# Adapter_UARTSPI_RS485.net
KiCad netlist of a schematic drawn in EAGLE
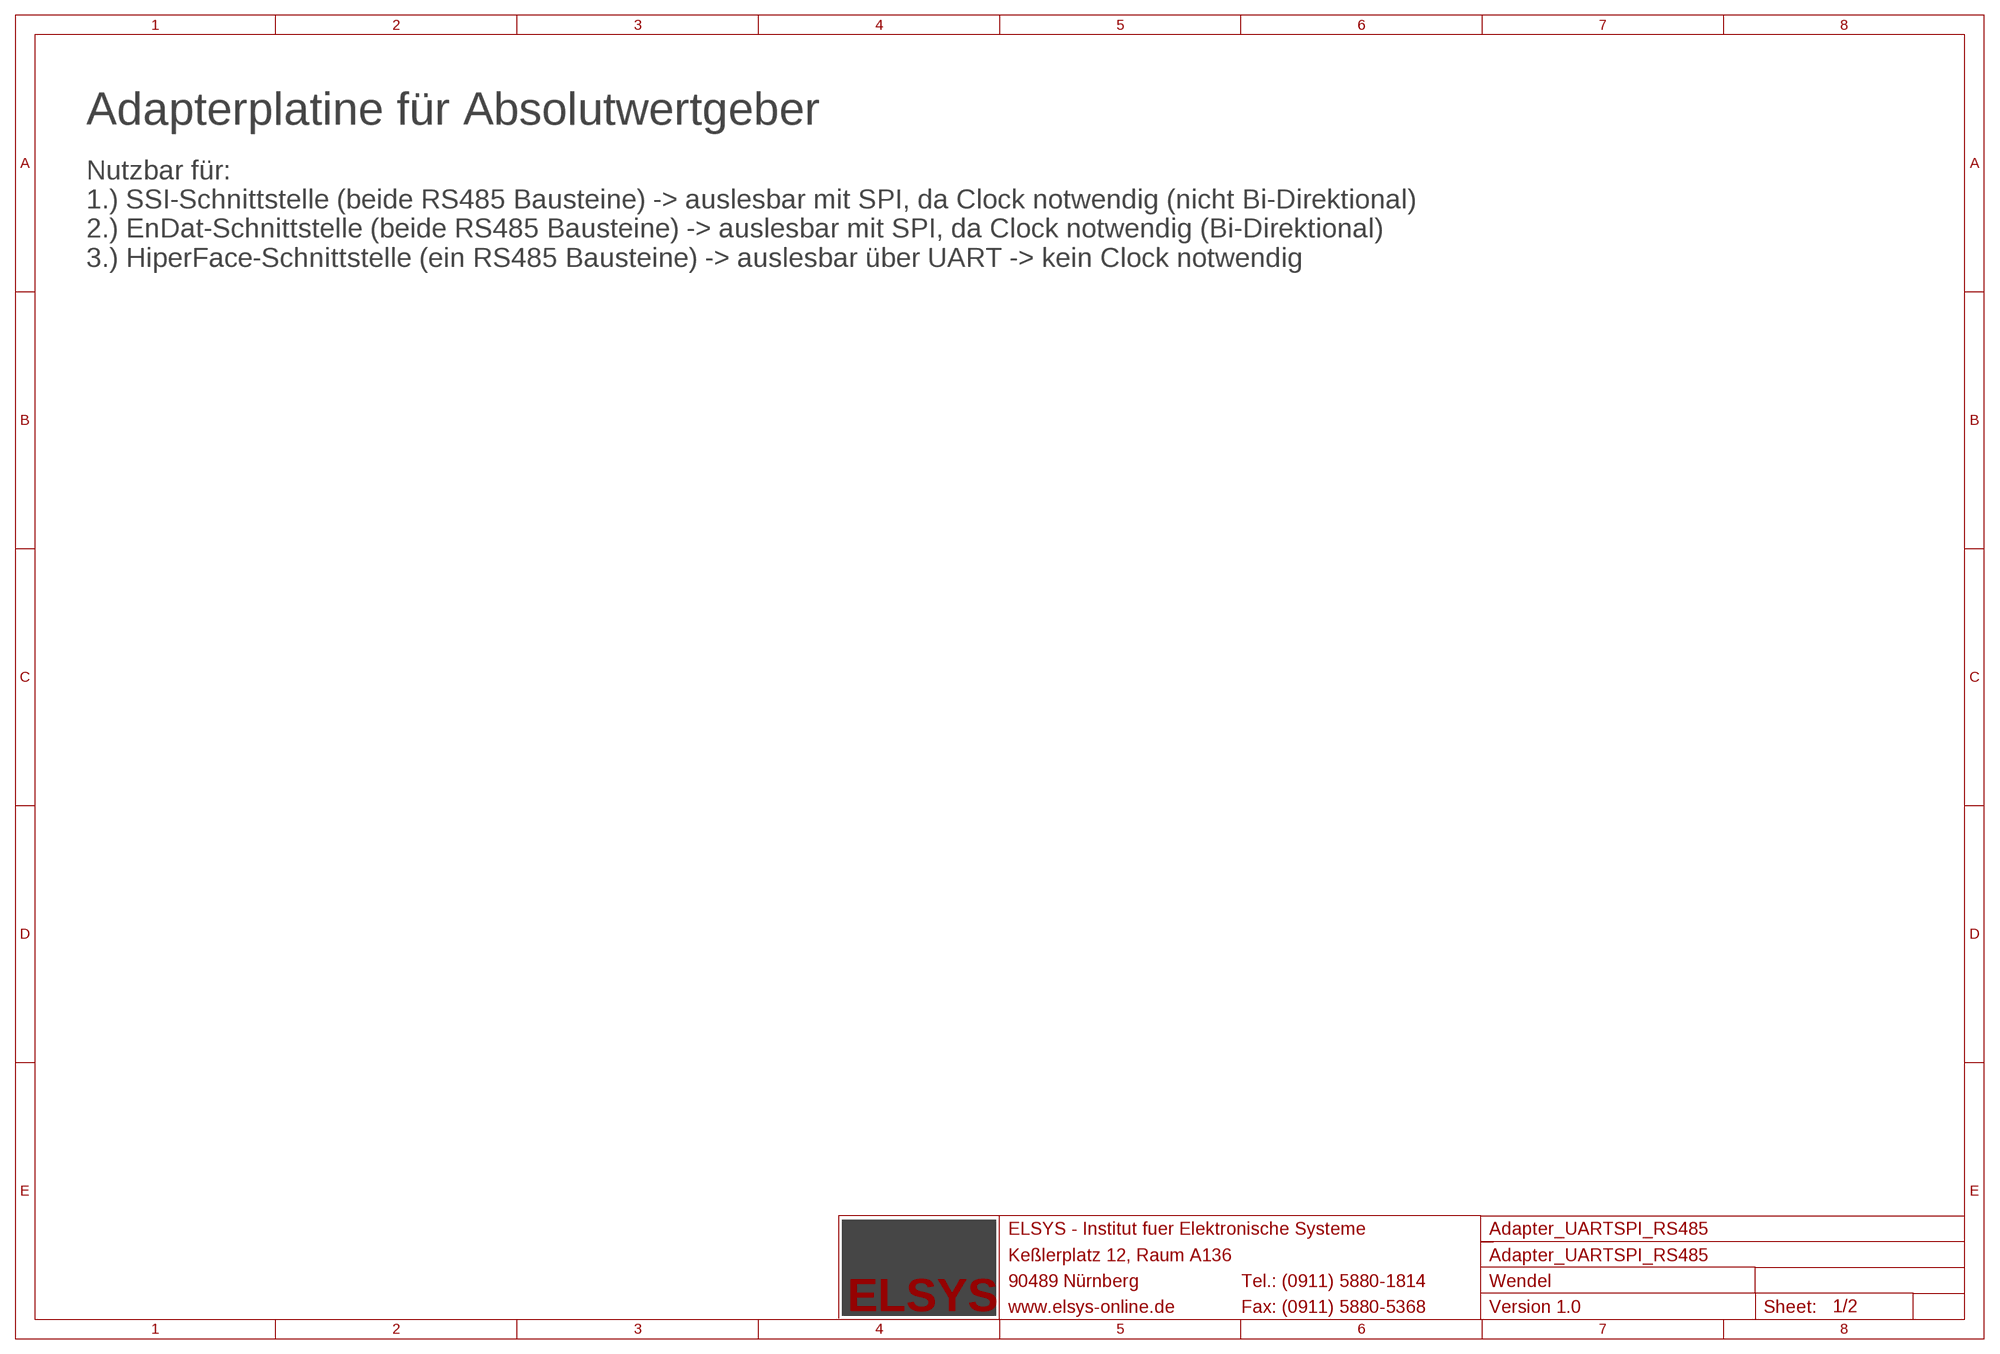
[diagram p0: schematic, sheet 1]
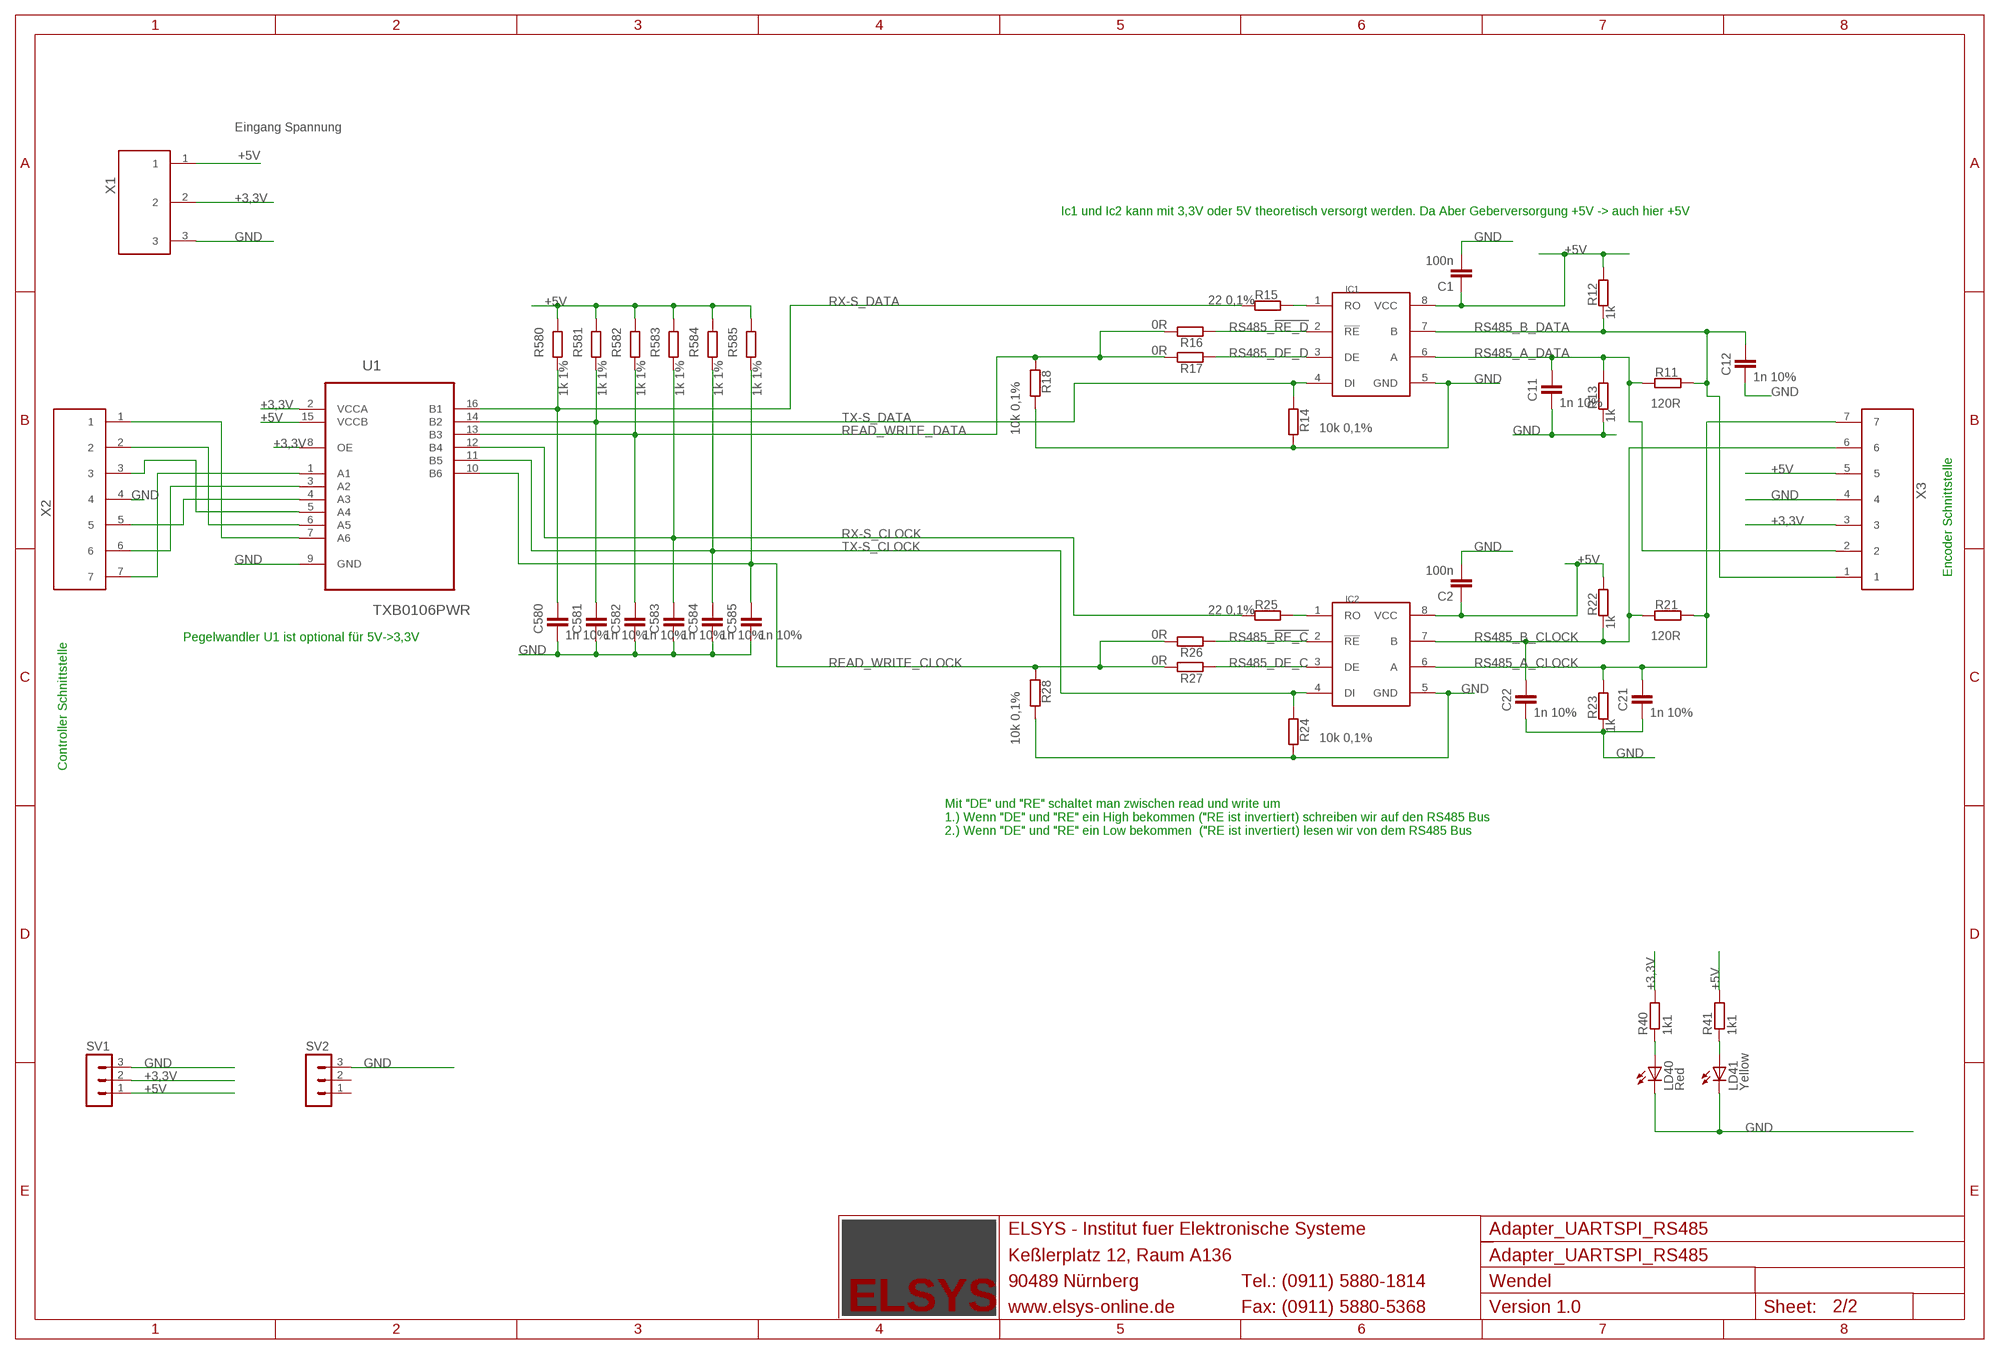
[diagram p1: schematic, sheet 2]

(export (version "E")
  (design (tool "Eeschema 10.0.6"))
  (components
    (comp (ref "C1")
      (value "100n")
      (footprint "eagle-import:SMD-0603")
      (libsource (lib "eagle-import") (part "C-EU0603"))
    )
    (comp (ref "C2")
      (value "100n")
      (footprint "eagle-import:SMD-0603")
      (libsource (lib "eagle-import") (part "C-EU0603"))
    )
    (comp (ref "C11")
      (value "1n 10%")
      (footprint "eagle-import:SMD-0603")
      (libsource (lib "eagle-import") (part "C-EU0603"))
    )
    (comp (ref "C12")
      (value "1n 10%")
      (footprint "eagle-import:SMD-0603")
      (libsource (lib "eagle-import") (part "C-EU0603"))
    )
    (comp (ref "C21")
      (value "1n 10%")
      (footprint "eagle-import:SMD-0603")
      (libsource (lib "eagle-import") (part "C-EU0603"))
    )
    (comp (ref "C22")
      (value "1n 10%")
      (footprint "eagle-import:SMD-0603")
      (libsource (lib "eagle-import") (part "C-EU0603"))
    )
    (comp (ref "C580")
      (value "1n 10%")
      (footprint "eagle-import:SMD-0603")
      (libsource (lib "eagle-import") (part "C-EU0603"))
    )
    (comp (ref "C581")
      (value "1n 10%")
      (footprint "eagle-import:SMD-0603")
      (libsource (lib "eagle-import") (part "C-EU0603"))
    )
    (comp (ref "C582")
      (value "1n 10%")
      (footprint "eagle-import:SMD-0603")
      (libsource (lib "eagle-import") (part "C-EU0603"))
    )
    (comp (ref "C583")
      (value "1n 10%")
      (footprint "eagle-import:SMD-0603")
      (libsource (lib "eagle-import") (part "C-EU0603"))
    )
    (comp (ref "C584")
      (value "1n 10%")
      (footprint "eagle-import:SMD-0603")
      (libsource (lib "eagle-import") (part "C-EU0603"))
    )
    (comp (ref "C585")
      (value "1n 10%")
      (footprint "eagle-import:SMD-0603")
      (libsource (lib "eagle-import") (part "C-EU0603"))
    )
    (comp (ref "IC1")
      (value "RS485-MAXIM")
      (footprint "eagle-import:SOIC8")
      (libsource (lib "eagle-import") (part "RS485-MAXIM"))
    )
    (comp (ref "IC2")
      (value "RS485-MAXIM")
      (footprint "eagle-import:SOIC8")
      (libsource (lib "eagle-import") (part "RS485-MAXIM"))
    )
    (comp (ref "LD40")
      (value "Red")
      (footprint "eagle-import:CHIP-LED0805")
      (libsource (lib "eagle-import") (part "LEDCHIP-LED0805"))
    )
    (comp (ref "LD41")
      (value "Yellow")
      (footprint "eagle-import:CHIP-LED0805")
      (libsource (lib "eagle-import") (part "LEDCHIP-LED0805"))
    )
    (comp (ref "R11")
      (value "120R")
      (footprint "eagle-import:R0603")
      (libsource (lib "eagle-import") (part "R-EU_R0603"))
    )
    (comp (ref "R12")
      (value "1k")
      (footprint "eagle-import:R0603")
      (libsource (lib "eagle-import") (part "R-EU_R0603"))
    )
    (comp (ref "R13")
      (value "1k")
      (footprint "eagle-import:R0603")
      (libsource (lib "eagle-import") (part "R-EU_R0603"))
    )
    (comp (ref "R14")
      (value "10k 0,1%")
      (footprint "eagle-import:R0603")
      (libsource (lib "eagle-import") (part "R-EU_R0603"))
    )
    (comp (ref "R15")
      (value "22 0,1%")
      (footprint "eagle-import:R0603")
      (libsource (lib "eagle-import") (part "R-EU_R0603"))
    )
    (comp (ref "R16")
      (value "0R")
      (footprint "eagle-import:R0603")
      (libsource (lib "eagle-import") (part "R-EU_R0603"))
    )
    (comp (ref "R17")
      (value "0R")
      (footprint "eagle-import:R0603")
      (libsource (lib "eagle-import") (part "R-EU_R0603"))
    )
    (comp (ref "R18")
      (value "10k 0,1%")
      (footprint "eagle-import:R0603")
      (libsource (lib "eagle-import") (part "R-EU_R0603"))
    )
    (comp (ref "R21")
      (value "120R")
      (footprint "eagle-import:R0603")
      (libsource (lib "eagle-import") (part "R-EU_R0603"))
    )
    (comp (ref "R22")
      (value "1k")
      (footprint "eagle-import:R0603")
      (libsource (lib "eagle-import") (part "R-EU_R0603"))
    )
    (comp (ref "R23")
      (value "1k")
      (footprint "eagle-import:R0603")
      (libsource (lib "eagle-import") (part "R-EU_R0603"))
    )
    (comp (ref "R24")
      (value "10k 0,1%")
      (footprint "eagle-import:R0603")
      (libsource (lib "eagle-import") (part "R-EU_R0603"))
    )
    (comp (ref "R25")
      (value "22 0,1%")
      (footprint "eagle-import:R0603")
      (libsource (lib "eagle-import") (part "R-EU_R0603"))
    )
    (comp (ref "R26")
      (value "0R")
      (footprint "eagle-import:R0603")
      (libsource (lib "eagle-import") (part "R-EU_R0603"))
    )
    (comp (ref "R27")
      (value "0R")
      (footprint "eagle-import:R0603")
      (libsource (lib "eagle-import") (part "R-EU_R0603"))
    )
    (comp (ref "R28")
      (value "10k 0,1%")
      (footprint "eagle-import:R0603")
      (libsource (lib "eagle-import") (part "R-EU_R0603"))
    )
    (comp (ref "R40")
      (value "1k1")
      (footprint "eagle-import:R0805")
      (libsource (lib "eagle-import") (part "R-EU_R0805"))
    )
    (comp (ref "R41")
      (value "1k1")
      (footprint "eagle-import:R0805")
      (libsource (lib "eagle-import") (part "R-EU_R0805"))
    )
    (comp (ref "R580")
      (value "1k 1%")
      (footprint "eagle-import:R0603")
      (libsource (lib "eagle-import") (part "R-EU_R0603"))
    )
    (comp (ref "R581")
      (value "1k 1%")
      (footprint "eagle-import:R0603")
      (libsource (lib "eagle-import") (part "R-EU_R0603"))
    )
    (comp (ref "R582")
      (value "1k 1%")
      (footprint "eagle-import:R0603")
      (libsource (lib "eagle-import") (part "R-EU_R0603"))
    )
    (comp (ref "R583")
      (value "1k 1%")
      (footprint "eagle-import:R0603")
      (libsource (lib "eagle-import") (part "R-EU_R0603"))
    )
    (comp (ref "R584")
      (value "1k 1%")
      (footprint "eagle-import:R0603")
      (libsource (lib "eagle-import") (part "R-EU_R0603"))
    )
    (comp (ref "R585")
      (value "1k 1%")
      (footprint "eagle-import:R0603")
      (libsource (lib "eagle-import") (part "R-EU_R0603"))
    )
    (comp (ref "SV1")
      (value "MA03-1")
      (footprint "eagle-import:MA03-1")
      (libsource (lib "eagle-import") (part "MA03-1"))
    )
    (comp (ref "SV2")
      (value "MA03-1")
      (footprint "eagle-import:MA03-1")
      (libsource (lib "eagle-import") (part "MA03-1"))
    )
    (comp (ref "U1")
      (value "TXB0106PWR")
      (footprint "eagle-import:SOP65P640X120-16N")
      (libsource (lib "eagle-import") (part "TXB0106PWR"))
    )
    (comp (ref "X1")
      (value "KLEMME_3POLIG_2,54")
      (footprint "eagle-import:KLEMME_3POLIG_2,54")
      (libsource (lib "eagle-import") (part "KLEMME_3POLIG_2,54"))
    )
    (comp (ref "X2")
      (value "KLEMME_7POLIG_2,54")
      (footprint "eagle-import:KLEMME_7POLIG_2,54")
      (libsource (lib "eagle-import") (part "KLEMME_7POLIG_2,54"))
    )
    (comp (ref "X3")
      (value "KLEMME_7POLIG_2,54")
      (footprint "eagle-import:KLEMME_7POLIG_2,54")
      (libsource (lib "eagle-import") (part "KLEMME_7POLIG_2,54"))
    )
  )
  (nets
    (net (code "1") (name "+3,3V") (class "Default")
      (node (ref "R40") (pin "2") (pinfunction "2_2") (pintype "passive"))
      (node (ref "SV1") (pin "2") (pinfunction "2_2") (pintype "passive"))
      (node (ref "U1") (pin "2") (pinfunction "VCCA_2") (pintype "power_in"))
      (node (ref "U1") (pin "8") (pinfunction "OE_8") (pintype "input"))
      (node (ref "X1") (pin "2") (pinfunction "2_2") (pintype "bidirectional"))
      (node (ref "X3") (pin "3") (pinfunction "3_3") (pintype "bidirectional"))
    )
    (net (code "2") (name "+5V") (class "Default")
      (node (ref "C1") (pin "1") (pinfunction "1_1") (pintype "passive"))
      (node (ref "C2") (pin "1") (pinfunction "1_1") (pintype "passive"))
      (node (ref "IC1") (pin "8") (pinfunction "VCC_8") (pintype "bidirectional"))
      (node (ref "IC2") (pin "8") (pinfunction "VCC_8") (pintype "bidirectional"))
      (node (ref "R12") (pin "1") (pinfunction "1_1") (pintype "passive"))
      (node (ref "R22") (pin "1") (pinfunction "1_1") (pintype "passive"))
      (node (ref "R41") (pin "2") (pinfunction "2_2") (pintype "passive"))
      (node (ref "R580") (pin "2") (pinfunction "2_2") (pintype "passive"))
      (node (ref "R581") (pin "2") (pinfunction "2_2") (pintype "passive"))
      (node (ref "R582") (pin "2") (pinfunction "2_2") (pintype "passive"))
      (node (ref "R583") (pin "2") (pinfunction "2_2") (pintype "passive"))
      (node (ref "R584") (pin "2") (pinfunction "2_2") (pintype "passive"))
      (node (ref "R585") (pin "2") (pinfunction "2_2") (pintype "passive"))
      (node (ref "SV1") (pin "1") (pinfunction "1_1") (pintype "passive"))
      (node (ref "U1") (pin "15") (pinfunction "VCCB_15") (pintype "power_in"))
      (node (ref "X1") (pin "1") (pinfunction "1_1") (pintype "bidirectional"))
      (node (ref "X3") (pin "5") (pinfunction "5_5") (pintype "bidirectional"))
    )
    (net (code "3") (name "GND") (class "Default")
      (node (ref "C1") (pin "2") (pinfunction "2_2") (pintype "passive"))
      (node (ref "C11") (pin "2") (pinfunction "2_2") (pintype "passive"))
      (node (ref "C12") (pin "2") (pinfunction "2_2") (pintype "passive"))
      (node (ref "C2") (pin "2") (pinfunction "2_2") (pintype "passive"))
      (node (ref "C21") (pin "2") (pinfunction "2_2") (pintype "passive"))
      (node (ref "C22") (pin "2") (pinfunction "2_2") (pintype "passive"))
      (node (ref "C580") (pin "2") (pinfunction "2_2") (pintype "passive"))
      (node (ref "C581") (pin "2") (pinfunction "2_2") (pintype "passive"))
      (node (ref "C582") (pin "2") (pinfunction "2_2") (pintype "passive"))
      (node (ref "C583") (pin "2") (pinfunction "2_2") (pintype "passive"))
      (node (ref "C584") (pin "2") (pinfunction "2_2") (pintype "passive"))
      (node (ref "C585") (pin "2") (pinfunction "2_2") (pintype "passive"))
      (node (ref "IC1") (pin "5") (pinfunction "GND_5") (pintype "bidirectional"))
      (node (ref "IC2") (pin "5") (pinfunction "GND_5") (pintype "bidirectional"))
      (node (ref "LD40") (pin "C") (pinfunction "C_C") (pintype "passive"))
      (node (ref "LD41") (pin "C") (pinfunction "C_C") (pintype "passive"))
      (node (ref "R13") (pin "2") (pinfunction "2_2") (pintype "passive"))
      (node (ref "R14") (pin "1") (pinfunction "1_1") (pintype "passive"))
      (node (ref "R18") (pin "1") (pinfunction "1_1") (pintype "passive"))
      (node (ref "R23") (pin "2") (pinfunction "2_2") (pintype "passive"))
      (node (ref "R24") (pin "1") (pinfunction "1_1") (pintype "passive"))
      (node (ref "R28") (pin "1") (pinfunction "1_1") (pintype "passive"))
      (node (ref "SV1") (pin "3") (pinfunction "3_3") (pintype "passive"))
      (node (ref "SV2") (pin "3") (pinfunction "3_3") (pintype "passive"))
      (node (ref "U1") (pin "9") (pinfunction "GND_9") (pintype "passive"))
      (node (ref "X1") (pin "3") (pinfunction "3_3") (pintype "bidirectional"))
      (node (ref "X2") (pin "4") (pinfunction "4_4") (pintype "bidirectional"))
      (node (ref "X3") (pin "4") (pinfunction "4_4") (pintype "bidirectional"))
    )
    (net (code "4") (name "Net-(IC1-RO)") (class "Default")
      (node (ref "IC1") (pin "1") (pinfunction "RO_1") (pintype "bidirectional"))
      (node (ref "R15") (pin "1") (pinfunction "1_1") (pintype "passive"))
    )
    (net (code "5") (name "Net-(IC2-RO)") (class "Default")
      (node (ref "IC2") (pin "1") (pinfunction "RO_1") (pintype "bidirectional"))
      (node (ref "R25") (pin "1") (pinfunction "1_1") (pintype "passive"))
    )
    (net (code "6") (name "Net-(LD40-PadA)") (class "Default")
      (node (ref "LD40") (pin "A") (pinfunction "A_A") (pintype "passive"))
      (node (ref "R40") (pin "1") (pinfunction "1_1") (pintype "passive"))
    )
    (net (code "7") (name "Net-(LD41-PadA)") (class "Default")
      (node (ref "LD41") (pin "A") (pinfunction "A_A") (pintype "passive"))
      (node (ref "R41") (pin "1") (pinfunction "1_1") (pintype "passive"))
    )
    (net (code "8") (name "Net-(U1-A1)") (class "Default")
      (node (ref "U1") (pin "1") (pinfunction "A1_1") (pintype "bidirectional"))
      (node (ref "X2") (pin "7") (pinfunction "7_7") (pintype "bidirectional"))
    )
    (net (code "9") (name "Net-(U1-A2)") (class "Default")
      (node (ref "U1") (pin "3") (pinfunction "A2_3") (pintype "bidirectional"))
      (node (ref "X2") (pin "6") (pinfunction "6_6") (pintype "bidirectional"))
    )
    (net (code "10") (name "Net-(U1-A3)") (class "Default")
      (node (ref "U1") (pin "4") (pinfunction "A3_4") (pintype "bidirectional"))
      (node (ref "X2") (pin "5") (pinfunction "5_5") (pintype "bidirectional"))
    )
    (net (code "11") (name "Net-(U1-A4)") (class "Default")
      (node (ref "U1") (pin "5") (pinfunction "A4_5") (pintype "bidirectional"))
      (node (ref "X2") (pin "3") (pinfunction "3_3") (pintype "bidirectional"))
    )
    (net (code "12") (name "Net-(U1-A5)") (class "Default")
      (node (ref "U1") (pin "6") (pinfunction "A5_6") (pintype "bidirectional"))
      (node (ref "X2") (pin "2") (pinfunction "2_2") (pintype "bidirectional"))
    )
    (net (code "13") (name "Net-(U1-A6)") (class "Default")
      (node (ref "U1") (pin "7") (pinfunction "A6_7") (pintype "bidirectional"))
      (node (ref "X2") (pin "1") (pinfunction "1_1") (pintype "bidirectional"))
    )
    (net (code "14") (name "READ_WRITE_CLOCK") (class "Default")
      (node (ref "C585") (pin "1") (pinfunction "1_1") (pintype "passive"))
      (node (ref "R26") (pin "1") (pinfunction "1_1") (pintype "passive"))
      (node (ref "R27") (pin "1") (pinfunction "1_1") (pintype "passive"))
      (node (ref "R28") (pin "2") (pinfunction "2_2") (pintype "passive"))
      (node (ref "R585") (pin "1") (pinfunction "1_1") (pintype "passive"))
      (node (ref "U1") (pin "10") (pinfunction "B6_10") (pintype "bidirectional"))
    )
    (net (code "15") (name "READ_WRITE_DATA") (class "Default")
      (node (ref "C582") (pin "1") (pinfunction "1_1") (pintype "passive"))
      (node (ref "R16") (pin "1") (pinfunction "1_1") (pintype "passive"))
      (node (ref "R17") (pin "1") (pinfunction "1_1") (pintype "passive"))
      (node (ref "R18") (pin "2") (pinfunction "2_2") (pintype "passive"))
      (node (ref "R582") (pin "1") (pinfunction "1_1") (pintype "passive"))
      (node (ref "U1") (pin "13") (pinfunction "B3_13") (pintype "bidirectional"))
    )
    (net (code "16") (name "RS485_A_CLOCK") (class "Default")
      (node (ref "C21") (pin "1") (pinfunction "1_1") (pintype "passive"))
      (node (ref "IC2") (pin "6") (pinfunction "A_6") (pintype "bidirectional"))
      (node (ref "R21") (pin "1") (pinfunction "1_1") (pintype "passive"))
      (node (ref "R23") (pin "1") (pinfunction "1_1") (pintype "passive"))
      (node (ref "X3") (pin "7") (pinfunction "7_7") (pintype "bidirectional"))
    )
    (net (code "17") (name "RS485_A_DATA") (class "Default")
      (node (ref "C11") (pin "1") (pinfunction "1_1") (pintype "passive"))
      (node (ref "IC1") (pin "6") (pinfunction "A_6") (pintype "bidirectional"))
      (node (ref "R11") (pin "2") (pinfunction "2_2") (pintype "passive"))
      (node (ref "R13") (pin "1") (pinfunction "1_1") (pintype "passive"))
      (node (ref "X3") (pin "2") (pinfunction "2_2") (pintype "bidirectional"))
    )
    (net (code "18") (name "RS485_B_CLOCK") (class "Default")
      (node (ref "C22") (pin "1") (pinfunction "1_1") (pintype "passive"))
      (node (ref "IC2") (pin "7") (pinfunction "B_7") (pintype "bidirectional"))
      (node (ref "R21") (pin "2") (pinfunction "2_2") (pintype "passive"))
      (node (ref "R22") (pin "2") (pinfunction "2_2") (pintype "passive"))
      (node (ref "X3") (pin "6") (pinfunction "6_6") (pintype "bidirectional"))
    )
    (net (code "19") (name "RS485_B_DATA") (class "Default")
      (node (ref "C12") (pin "1") (pinfunction "1_1") (pintype "passive"))
      (node (ref "IC1") (pin "7") (pinfunction "B_7") (pintype "bidirectional"))
      (node (ref "R11") (pin "1") (pinfunction "1_1") (pintype "passive"))
      (node (ref "R12") (pin "2") (pinfunction "2_2") (pintype "passive"))
      (node (ref "X3") (pin "1") (pinfunction "1_1") (pintype "bidirectional"))
    )
    (net (code "20") (name "RS485_DE_C") (class "Default")
      (node (ref "IC2") (pin "3") (pinfunction "DE_3") (pintype "bidirectional"))
      (node (ref "R27") (pin "2") (pinfunction "2_2") (pintype "passive"))
    )
    (net (code "21") (name "RS485_DE_D") (class "Default")
      (node (ref "IC1") (pin "3") (pinfunction "DE_3") (pintype "bidirectional"))
      (node (ref "R17") (pin "2") (pinfunction "2_2") (pintype "passive"))
    )
    (net (code "22") (name "RS485_~{RE_C}") (class "Default")
      (node (ref "IC2") (pin "2") (pinfunction "~{RE}_2") (pintype "bidirectional"))
      (node (ref "R26") (pin "2") (pinfunction "2_2") (pintype "passive"))
    )
    (net (code "23") (name "RS485_~{RE_D}") (class "Default")
      (node (ref "IC1") (pin "2") (pinfunction "~{RE}_2") (pintype "bidirectional"))
      (node (ref "R16") (pin "2") (pinfunction "2_2") (pintype "passive"))
    )
    (net (code "24") (name "RX-S_CLOCK") (class "Default")
      (node (ref "C583") (pin "1") (pinfunction "1_1") (pintype "passive"))
      (node (ref "R25") (pin "2") (pinfunction "2_2") (pintype "passive"))
      (node (ref "R583") (pin "1") (pinfunction "1_1") (pintype "passive"))
      (node (ref "U1") (pin "12") (pinfunction "B4_12") (pintype "bidirectional"))
    )
    (net (code "25") (name "RX-S_DATA") (class "Default")
      (node (ref "C580") (pin "1") (pinfunction "1_1") (pintype "passive"))
      (node (ref "R15") (pin "2") (pinfunction "2_2") (pintype "passive"))
      (node (ref "R580") (pin "1") (pinfunction "1_1") (pintype "passive"))
      (node (ref "U1") (pin "16") (pinfunction "B1_16") (pintype "bidirectional"))
    )
    (net (code "26") (name "TX-S_CLOCK") (class "Default")
      (node (ref "C584") (pin "1") (pinfunction "1_1") (pintype "passive"))
      (node (ref "IC2") (pin "4") (pinfunction "DI_4") (pintype "bidirectional"))
      (node (ref "R24") (pin "2") (pinfunction "2_2") (pintype "passive"))
      (node (ref "R584") (pin "1") (pinfunction "1_1") (pintype "passive"))
      (node (ref "U1") (pin "11") (pinfunction "B5_11") (pintype "bidirectional"))
    )
    (net (code "27") (name "TX-S_DATA") (class "Default")
      (node (ref "C581") (pin "1") (pinfunction "1_1") (pintype "passive"))
      (node (ref "IC1") (pin "4") (pinfunction "DI_4") (pintype "bidirectional"))
      (node (ref "R14") (pin "2") (pinfunction "2_2") (pintype "passive"))
      (node (ref "R581") (pin "1") (pinfunction "1_1") (pintype "passive"))
      (node (ref "U1") (pin "14") (pinfunction "B2_14") (pintype "bidirectional"))
    )
    (net (code "28") (name "unconnected-(SV2-Pad1)") (class "Default")
      (node (ref "SV2") (pin "1") (pinfunction "1_1") (pintype "passive"))
    )
    (net (code "29") (name "unconnected-(SV2-Pad2)") (class "Default")
      (node (ref "SV2") (pin "2") (pinfunction "2_2") (pintype "passive"))
    )
  )
)
